# schematics.net
KiCad netlist of a schematic drawn in EAGLE
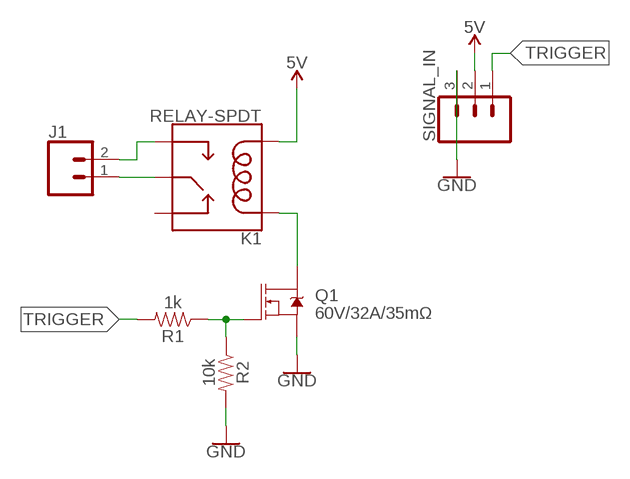
[diagram p0: schematic, sheet 1]

(export (version "E")
  (design (tool "Eeschema 10.0.6"))
  (components
    (comp (ref "J1")
      (value "CONN_025MM")
      (footprint "eagle-import:SCREWTERMINAL-5MM-2")
      (libsource (lib "eagle-import") (part "CONN_025MM"))
    )
    (comp (ref "K1")
      (value "RELAY-SPDT")
      (footprint "eagle-import:RELAY_G5LE")
      (libsource (lib "eagle-import") (part "RELAY-SPDT"))
    )
    (comp (ref "Q1")
      (value "60V/32A/35mΩ")
      (footprint "eagle-import:TO220V")
      (libsource (lib "eagle-import") (part "MOSFET-NCH-FQP30N06L"))
    )
    (comp (ref "R1")
      (value "1k")
      (footprint "eagle-import:AXIAL-0.3")
      (libsource (lib "eagle-import") (part "1KOHM-HORIZ-1/4W-1%"))
    )
    (comp (ref "R2")
      (value "10k")
      (footprint "eagle-import:AXIAL-0.3")
      (libsource (lib "eagle-import") (part "1KOHM-HORIZ-1/4W-1%"))
    )
    (comp (ref "SIGNAL_IN")
      (value "CONN_03")
      (footprint "eagle-import:1X03")
      (libsource (lib "eagle-import") (part "CONN_03"))
    )
  )
  (nets
    (net (code "1") (name "5V") (class "Default")
      (node (ref "K1") (pin "5") (pinfunction "COIL2_5") (pintype "bidirectional"))
      (node (ref "SIGNAL_IN") (pin "2") (pinfunction "2_2") (pintype "passive"))
    )
    (net (code "2") (name "GND") (class "Default")
      (node (ref "Q1") (pin "3") (pinfunction "S_3") (pintype "bidirectional"))
      (node (ref "R2") (pin "P$2") (pinfunction "2_P$2") (pintype "passive"))
      (node (ref "SIGNAL_IN") (pin "3") (pinfunction "3_3") (pintype "passive"))
    )
    (net (code "3") (name "Net-(K1-COIL1)") (class "Default")
      (node (ref "K1") (pin "2") (pinfunction "COIL1_2") (pintype "bidirectional"))
      (node (ref "Q1") (pin "2") (pinfunction "D_2") (pintype "bidirectional"))
    )
    (net (code "4") (name "Net-(K1-MAIN)") (class "Default")
      (node (ref "J1") (pin "1") (pinfunction "1_1") (pintype "passive"))
      (node (ref "K1") (pin "1") (pinfunction "MAIN_1") (pintype "bidirectional"))
    )
    (net (code "5") (name "Net-(K1-NO)") (class "Default")
      (node (ref "J1") (pin "2") (pinfunction "2_2") (pintype "passive"))
      (node (ref "K1") (pin "3") (pinfunction "NO_3") (pintype "bidirectional"))
    )
    (net (code "6") (name "Net-(Q1-G)") (class "Default")
      (node (ref "Q1") (pin "1") (pinfunction "G_1") (pintype "bidirectional"))
      (node (ref "R1") (pin "P$1") (pinfunction "1_P$1") (pintype "passive"))
      (node (ref "R2") (pin "P$1") (pinfunction "1_P$1") (pintype "passive"))
    )
    (net (code "7") (name "TRIGGER") (class "Default")
      (node (ref "R1") (pin "P$2") (pinfunction "2_P$2") (pintype "passive"))
      (node (ref "SIGNAL_IN") (pin "1") (pinfunction "1_1") (pintype "passive"))
    )
    (net (code "8") (name "unconnected-(K1-NC-Pad4)") (class "Default")
      (node (ref "K1") (pin "4") (pinfunction "NC_4") (pintype "bidirectional"))
    )
  )
)
